# colpitts.net
KiCad netlist of a schematic drawn in EAGLE
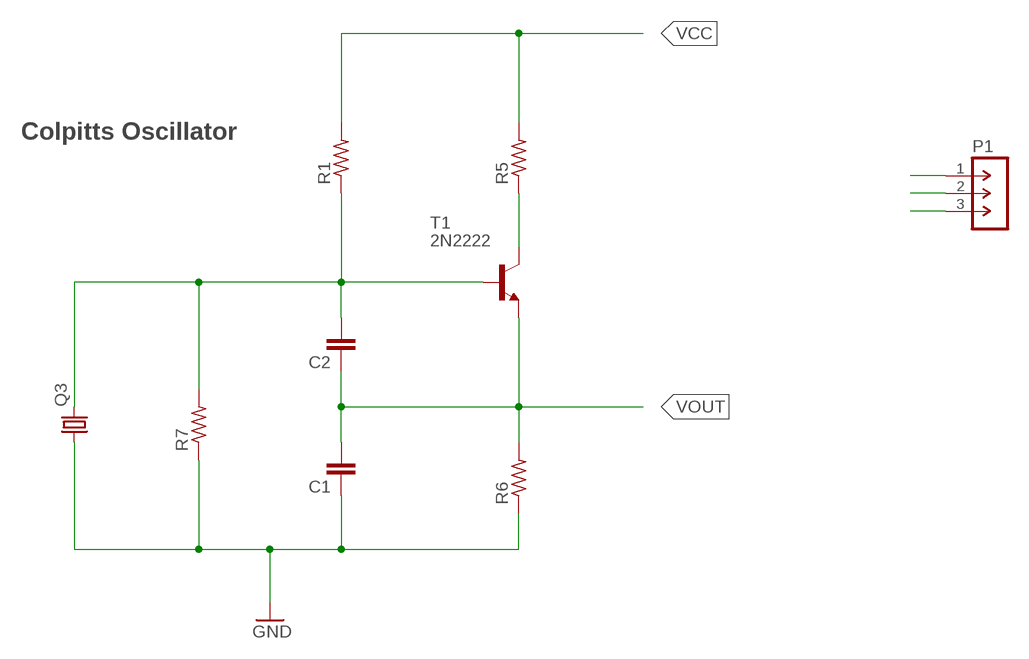
[diagram p0: schematic, sheet 1]

(export (version "E")
  (design (tool "Eeschema 10.0.6"))
  (components
    (comp (ref "C1")
      (value "C2,5-3")
      (footprint "eagle-import:C2.5-3")
      (libsource (lib "eagle-import") (part "C2,5-3"))
    )
    (comp (ref "C2")
      (value "C2,5-3")
      (footprint "eagle-import:C2.5-3")
      (libsource (lib "eagle-import") (part "C2,5-3"))
    )
    (comp (ref "P1")
      (value "M-1X03-SIP-100-40")
      (footprint "eagle-import:SIP-100-03-40")
      (libsource (lib "eagle-import") (part "M-1X03-SIP-100-40"))
    )
    (comp (ref "Q3")
      (value "CRYSTALTC26V")
      (footprint "eagle-import:TC26V")
      (libsource (lib "eagle-import") (part "CRYSTALTC26V"))
    )
    (comp (ref "R1")
      (value "R-US_0204/5")
      (footprint "eagle-import:0204_5")
      (libsource (lib "eagle-import") (part "R-US_0204/5"))
    )
    (comp (ref "R5")
      (value "R-US_0204/5")
      (footprint "eagle-import:0204_5")
      (libsource (lib "eagle-import") (part "R-US_0204/5"))
    )
    (comp (ref "R6")
      (value "R-US_0204/5")
      (footprint "eagle-import:0204_5")
      (libsource (lib "eagle-import") (part "R-US_0204/5"))
    )
    (comp (ref "R7")
      (value "R-US_0204/5")
      (footprint "eagle-import:0204_5")
      (libsource (lib "eagle-import") (part "R-US_0204/5"))
    )
    (comp (ref "T1")
      (value "2N2222")
      (footprint "eagle-import:TO92-EBC-OVAL")
      (libsource (lib "eagle-import") (part "2N2222"))
    )
  )
  (nets
    (net (code "1") (name "GND") (class "Default")
      (node (ref "C1") (pin "1") (pinfunction "1_1") (pintype "passive"))
      (node (ref "P1") (pin "3") (pinfunction "3_3") (pintype "passive"))
      (node (ref "Q3") (pin "1") (pinfunction "1_1") (pintype "passive"))
      (node (ref "R6") (pin "1") (pinfunction "1_1") (pintype "passive"))
      (node (ref "R7") (pin "1") (pinfunction "1_1") (pintype "passive"))
    )
    (net (code "2") (name "Net-(C2-Pad2)") (class "Default")
      (node (ref "C2") (pin "2") (pinfunction "2_2") (pintype "passive"))
      (node (ref "Q3") (pin "2") (pinfunction "2_2") (pintype "passive"))
      (node (ref "R1") (pin "1") (pinfunction "1_1") (pintype "passive"))
      (node (ref "R7") (pin "2") (pinfunction "2_2") (pintype "passive"))
      (node (ref "T1") (pin "B") (pinfunction "B_B") (pintype "passive"))
    )
    (net (code "3") (name "Net-(R5-Pad1)") (class "Default")
      (node (ref "R5") (pin "1") (pinfunction "1_1") (pintype "passive"))
      (node (ref "T1") (pin "C") (pinfunction "C_C") (pintype "passive"))
    )
    (net (code "4") (name "VCC") (class "Default")
      (node (ref "P1") (pin "1") (pinfunction "1_1") (pintype "passive"))
      (node (ref "R1") (pin "2") (pinfunction "2_2") (pintype "passive"))
      (node (ref "R5") (pin "2") (pinfunction "2_2") (pintype "passive"))
    )
    (net (code "5") (name "VOUT") (class "Default")
      (node (ref "C1") (pin "2") (pinfunction "2_2") (pintype "passive"))
      (node (ref "C2") (pin "1") (pinfunction "1_1") (pintype "passive"))
      (node (ref "P1") (pin "2") (pinfunction "2_2") (pintype "passive"))
      (node (ref "R6") (pin "2") (pinfunction "2_2") (pintype "passive"))
      (node (ref "T1") (pin "E") (pinfunction "E_E") (pintype "passive"))
    )
  )
)
